# TG16_EXP_RGBSV_RevB.net
KiCad netlist of a schematic drawn in EAGLE
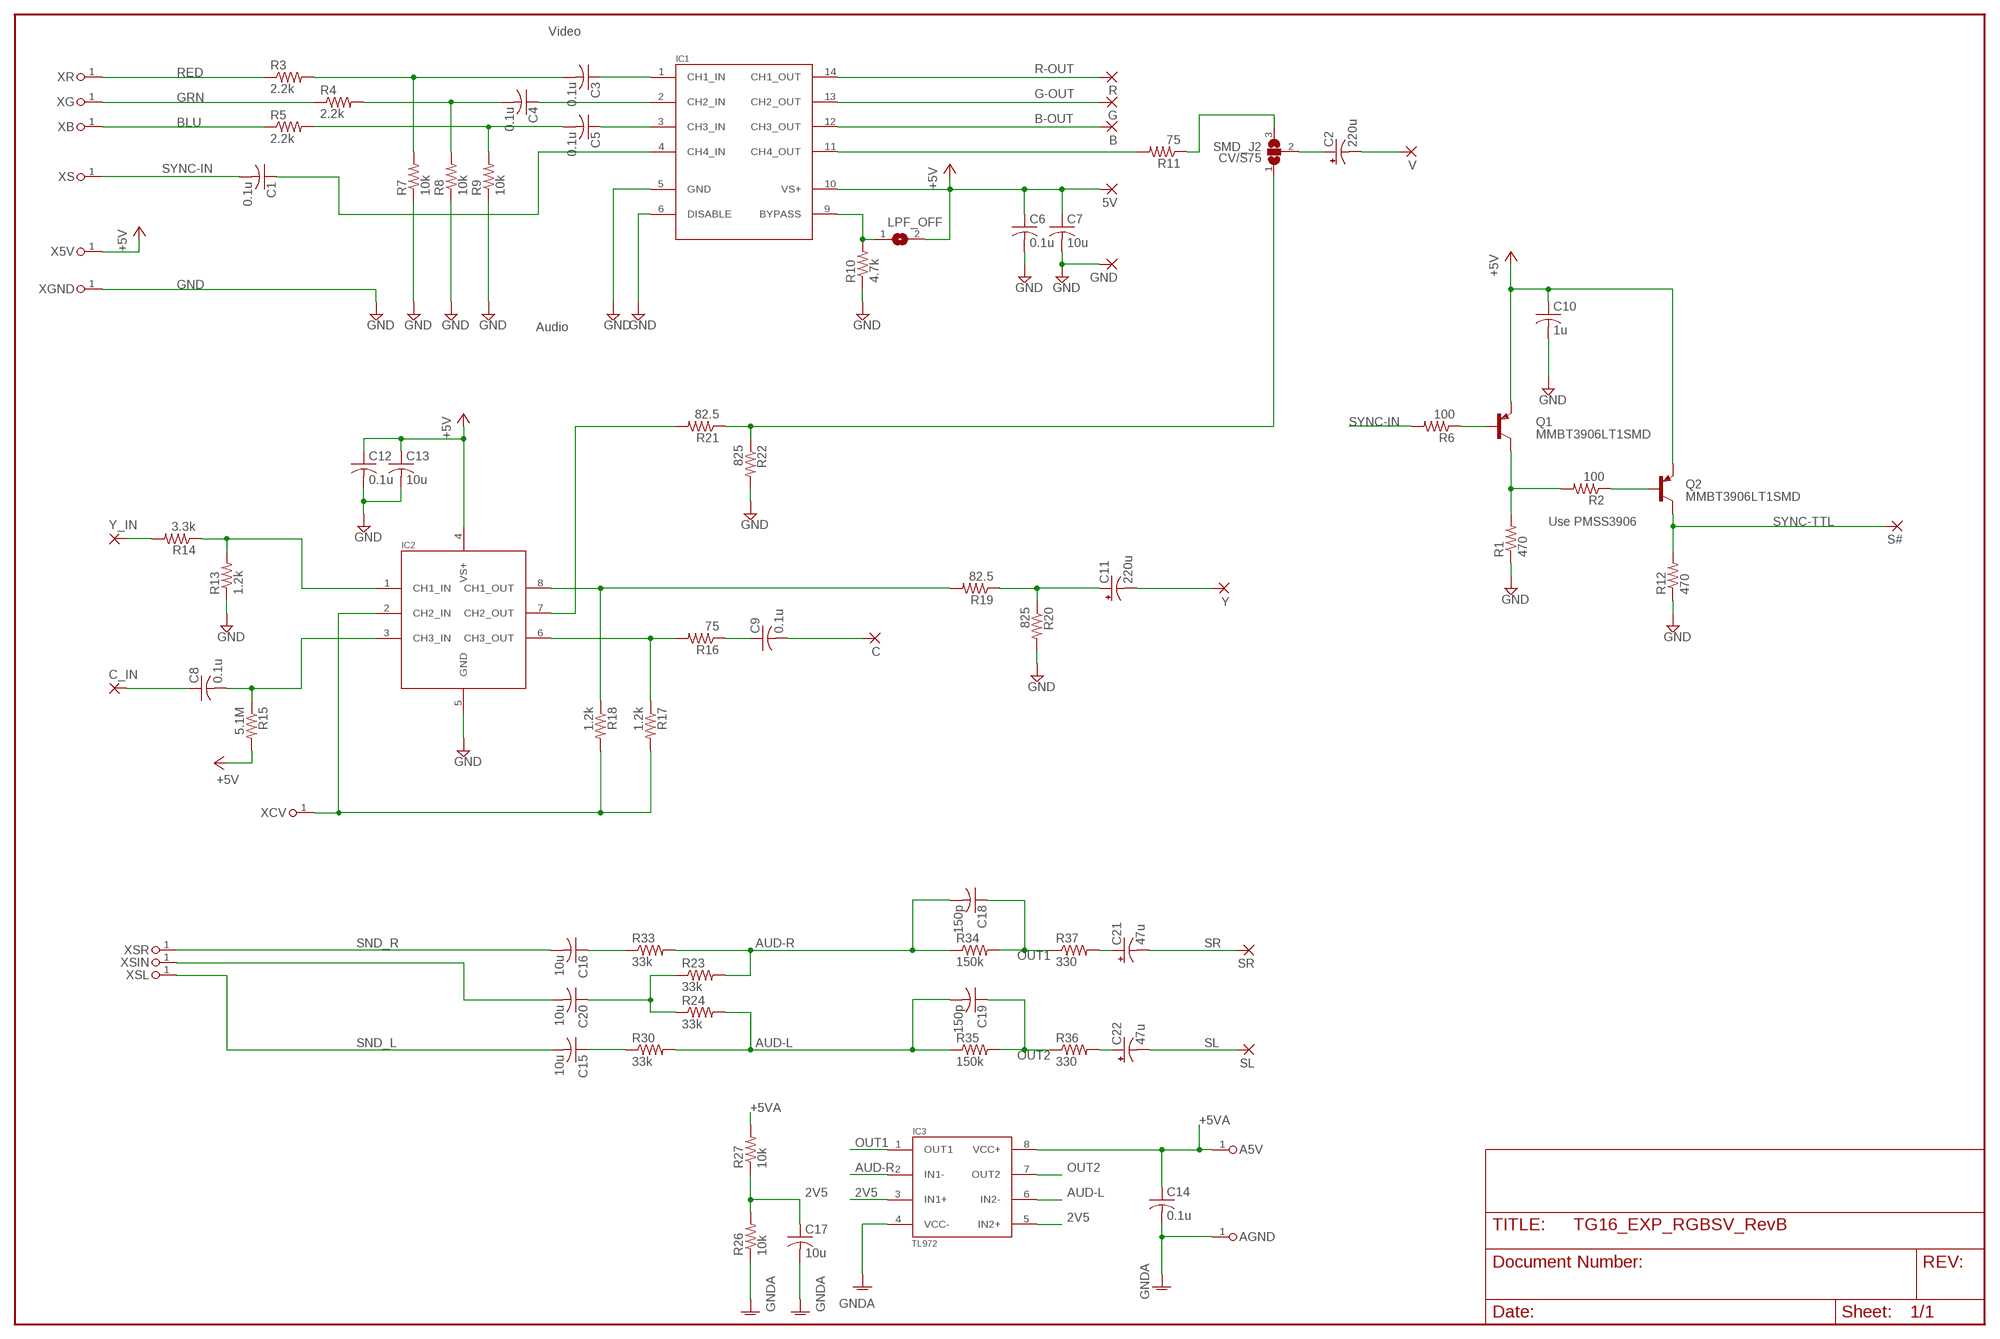
[diagram p0: schematic, sheet 1]

(export (version "E")
  (design (tool "Eeschema 10.0.6"))
  (components
    (comp (ref "5V")
      (value "SMD2")
      (footprint "eagle-import:SMD1,27-2,54")
      (libsource (lib "eagle-import") (part "SMD2"))
    )
    (comp (ref "A5V")
      (value "PINHD-1X1")
      (footprint "eagle-import:1X01")
      (libsource (lib "eagle-import") (part "PINHD-1X1"))
    )
    (comp (ref "AGND")
      (value "PINHD-1X1")
      (footprint "eagle-import:1X01")
      (libsource (lib "eagle-import") (part "PINHD-1X1"))
    )
    (comp (ref "B")
      (value "SMD2")
      (footprint "eagle-import:SMD1,27-2,54")
      (libsource (lib "eagle-import") (part "SMD2"))
    )
    (comp (ref "C")
      (value "SMD2")
      (footprint "eagle-import:SMD1,27-2,54")
      (libsource (lib "eagle-import") (part "SMD2"))
    )
    (comp (ref "C1")
      (value "0.1u")
      (footprint "eagle-import:C0603")
      (libsource (lib "eagle-import") (part "C-USC0603"))
    )
    (comp (ref "C2")
      (value "220u")
      (footprint "eagle-import:CT3528")
      (libsource (lib "eagle-import") (part "rcl_334_CPOL-USCT3528"))
    )
    (comp (ref "C3")
      (value "0.1u")
      (footprint "eagle-import:C0603")
      (libsource (lib "eagle-import") (part "C-USC0603"))
    )
    (comp (ref "C4")
      (value "0.1u")
      (footprint "eagle-import:C0603")
      (libsource (lib "eagle-import") (part "C-USC0603"))
    )
    (comp (ref "C5")
      (value "0.1u")
      (footprint "eagle-import:C0603")
      (libsource (lib "eagle-import") (part "C-USC0603"))
    )
    (comp (ref "C6")
      (value "0.1u")
      (footprint "eagle-import:C0603")
      (libsource (lib "eagle-import") (part "C-USC0603"))
    )
    (comp (ref "C7")
      (value "10u")
      (footprint "eagle-import:C1206")
      (libsource (lib "eagle-import") (part "C-USC1206"))
    )
    (comp (ref "C8")
      (value "0.1u")
      (footprint "eagle-import:C0603")
      (libsource (lib "eagle-import") (part "C-USC0603"))
    )
    (comp (ref "C9")
      (value "0.1u")
      (footprint "eagle-import:C0603")
      (libsource (lib "eagle-import") (part "C-USC0603"))
    )
    (comp (ref "C10")
      (value "1u")
      (footprint "eagle-import:C0603")
      (libsource (lib "eagle-import") (part "C-USC0603"))
    )
    (comp (ref "C11")
      (value "220u")
      (footprint "eagle-import:CT3528")
      (libsource (lib "eagle-import") (part "rcl_334_CPOL-USCT3528"))
    )
    (comp (ref "C12")
      (value "0.1u")
      (footprint "eagle-import:C0603")
      (libsource (lib "eagle-import") (part "C-USC0603"))
    )
    (comp (ref "C13")
      (value "10u")
      (footprint "eagle-import:C1206")
      (libsource (lib "eagle-import") (part "C-USC1206"))
    )
    (comp (ref "C14")
      (value "0.1u")
      (footprint "eagle-import:C0603")
      (libsource (lib "eagle-import") (part "C-USC0603"))
    )
    (comp (ref "C15")
      (value "10u")
      (footprint "eagle-import:C0805")
      (libsource (lib "eagle-import") (part "C-USC0805"))
    )
    (comp (ref "C16")
      (value "10u")
      (footprint "eagle-import:C0805")
      (libsource (lib "eagle-import") (part "C-USC0805"))
    )
    (comp (ref "C17")
      (value "10u")
      (footprint "eagle-import:C1206")
      (libsource (lib "eagle-import") (part "C-USC1206"))
    )
    (comp (ref "C18")
      (value "150p")
      (footprint "eagle-import:C0603")
      (libsource (lib "eagle-import") (part "C-USC0603"))
    )
    (comp (ref "C19")
      (value "150p")
      (footprint "eagle-import:C0603")
      (libsource (lib "eagle-import") (part "C-USC0603"))
    )
    (comp (ref "C20")
      (value "10u")
      (footprint "eagle-import:C0805")
      (libsource (lib "eagle-import") (part "C-USC0805"))
    )
    (comp (ref "C21")
      (value "47u")
      (footprint "eagle-import:CT3528")
      (libsource (lib "eagle-import") (part "CPOL-USCT3528"))
    )
    (comp (ref "C22")
      (value "47u")
      (footprint "eagle-import:CT3528")
      (libsource (lib "eagle-import") (part "CPOL-USCT3528"))
    )
    (comp (ref "CV/S75")
      (value "SMD_J2")
      (footprint "eagle-import:SJ_2")
      (libsource (lib "eagle-import") (part "SMD_J2"))
    )
    (comp (ref "C_IN")
      (value "SMD2")
      (footprint "eagle-import:SMD1,27-2,54")
      (libsource (lib "eagle-import") (part "SMD2"))
    )
    (comp (ref "G")
      (value "SMD2")
      (footprint "eagle-import:SMD1,27-2,54")
      (libsource (lib "eagle-import") (part "SMD2"))
    )
    (comp (ref "GND")
      (value "SMD2")
      (footprint "eagle-import:SMD1,27-2,54")
      (libsource (lib "eagle-import") (part "SMD2"))
    )
    (comp (ref "IC1")
      (value "THS7374TSSOP14_LONG")
      (footprint "eagle-import:TSSOP14LONG")
      (libsource (lib "eagle-import") (part "THS7374TSSOP14_LONG"))
    )
    (comp (ref "IC2")
      (value "THS7314")
      (footprint "eagle-import:SOIC8")
      (libsource (lib "eagle-import") (part "THS7314"))
    )
    (comp (ref "IC3")
      (value "TL972")
      (footprint "eagle-import:SOIC8")
      (libsource (lib "eagle-import") (part "TL972"))
    )
    (comp (ref "LPF_OFF")
      (value "SMD_J")
      (footprint "eagle-import:SJ")
      (libsource (lib "eagle-import") (part "SMD_J"))
    )
    (comp (ref "Q1")
      (value "MMBT3906LT1SMD")
      (footprint "eagle-import:SOT23-BEC")
      (libsource (lib "eagle-import") (part "MMBT3906SMDLT1"))
    )
    (comp (ref "Q2")
      (value "MMBT3906LT1SMD")
      (footprint "eagle-import:SOT23-BEC")
      (libsource (lib "eagle-import") (part "MMBT3906SMDLT1"))
    )
    (comp (ref "R")
      (value "SMD2")
      (footprint "eagle-import:SMD1,27-2,54")
      (libsource (lib "eagle-import") (part "SMD2"))
    )
    (comp (ref "R1")
      (value "470")
      (footprint "eagle-import:R0603")
      (libsource (lib "eagle-import") (part "R-US_R0603"))
    )
    (comp (ref "R2")
      (value "100")
      (footprint "eagle-import:R0603")
      (libsource (lib "eagle-import") (part "R-US_R0603"))
    )
    (comp (ref "R3")
      (value "2.2k")
      (footprint "eagle-import:R0603")
      (libsource (lib "eagle-import") (part "R-US_R0603"))
    )
    (comp (ref "R4")
      (value "2.2k")
      (footprint "eagle-import:R0603")
      (libsource (lib "eagle-import") (part "R-US_R0603"))
    )
    (comp (ref "R5")
      (value "2.2k")
      (footprint "eagle-import:R0603")
      (libsource (lib "eagle-import") (part "R-US_R0603"))
    )
    (comp (ref "R6")
      (value "100")
      (footprint "eagle-import:R0603")
      (libsource (lib "eagle-import") (part "R-US_R0603"))
    )
    (comp (ref "R7")
      (value "10k")
      (footprint "eagle-import:R0603")
      (libsource (lib "eagle-import") (part "R-US_R0603"))
    )
    (comp (ref "R8")
      (value "10k")
      (footprint "eagle-import:R0603")
      (libsource (lib "eagle-import") (part "R-US_R0603"))
    )
    (comp (ref "R9")
      (value "10k")
      (footprint "eagle-import:R0603")
      (libsource (lib "eagle-import") (part "R-US_R0603"))
    )
    (comp (ref "R10")
      (value "4.7k")
      (footprint "eagle-import:R0603")
      (libsource (lib "eagle-import") (part "R-US_R0603"))
    )
    (comp (ref "R11")
      (value "75")
      (footprint "eagle-import:R0603")
      (libsource (lib "eagle-import") (part "R-US_R0603"))
    )
    (comp (ref "R12")
      (value "470")
      (footprint "eagle-import:R0603")
      (libsource (lib "eagle-import") (part "R-US_R0603"))
    )
    (comp (ref "R13")
      (value "1.2k")
      (footprint "eagle-import:R0603")
      (libsource (lib "eagle-import") (part "R-US_R0603"))
    )
    (comp (ref "R14")
      (value "3.3k")
      (footprint "eagle-import:R0603")
      (libsource (lib "eagle-import") (part "R-US_R0603"))
    )
    (comp (ref "R15")
      (value "5.1M")
      (footprint "eagle-import:R0603")
      (libsource (lib "eagle-import") (part "R-US_R0603"))
    )
    (comp (ref "R16")
      (value "75")
      (footprint "eagle-import:R0603")
      (libsource (lib "eagle-import") (part "R-US_R0603"))
    )
    (comp (ref "R17")
      (value "1.2k")
      (footprint "eagle-import:R0603")
      (libsource (lib "eagle-import") (part "R-US_R0603"))
    )
    (comp (ref "R18")
      (value "1.2k")
      (footprint "eagle-import:R0603")
      (libsource (lib "eagle-import") (part "R-US_R0603"))
    )
    (comp (ref "R19")
      (value "82.5")
      (footprint "eagle-import:R0603")
      (libsource (lib "eagle-import") (part "R-US_R0603"))
    )
    (comp (ref "R20")
      (value "825")
      (footprint "eagle-import:R0603")
      (libsource (lib "eagle-import") (part "R-US_R0603"))
    )
    (comp (ref "R21")
      (value "82.5")
      (footprint "eagle-import:R0603")
      (libsource (lib "eagle-import") (part "R-US_R0603"))
    )
    (comp (ref "R22")
      (value "825")
      (footprint "eagle-import:R0603")
      (libsource (lib "eagle-import") (part "R-US_R0603"))
    )
    (comp (ref "R23")
      (value "33k")
      (footprint "eagle-import:R0603")
      (libsource (lib "eagle-import") (part "R-US_R0603"))
    )
    (comp (ref "R24")
      (value "33k")
      (footprint "eagle-import:R0603")
      (libsource (lib "eagle-import") (part "R-US_R0603"))
    )
    (comp (ref "R26")
      (value "10k")
      (footprint "eagle-import:R0603")
      (libsource (lib "eagle-import") (part "R-US_R0603"))
    )
    (comp (ref "R27")
      (value "10k")
      (footprint "eagle-import:R0603")
      (libsource (lib "eagle-import") (part "R-US_R0603"))
    )
    (comp (ref "R30")
      (value "33k")
      (footprint "eagle-import:R0603")
      (libsource (lib "eagle-import") (part "R-US_R0603"))
    )
    (comp (ref "R33")
      (value "33k")
      (footprint "eagle-import:R0603")
      (libsource (lib "eagle-import") (part "R-US_R0603"))
    )
    (comp (ref "R34")
      (value "150k")
      (footprint "eagle-import:R0603")
      (libsource (lib "eagle-import") (part "R-US_R0603"))
    )
    (comp (ref "R35")
      (value "150k")
      (footprint "eagle-import:R0603")
      (libsource (lib "eagle-import") (part "R-US_R0603"))
    )
    (comp (ref "R36")
      (value "330")
      (footprint "eagle-import:R0603")
      (libsource (lib "eagle-import") (part "R-US_R0603"))
    )
    (comp (ref "R37")
      (value "330")
      (footprint "eagle-import:R0603")
      (libsource (lib "eagle-import") (part "R-US_R0603"))
    )
    (comp (ref "S#")
      (value "SMD2")
      (footprint "eagle-import:SMD1,27-2,54")
      (libsource (lib "eagle-import") (part "SMD2"))
    )
    (comp (ref "SL")
      (value "SMD2")
      (footprint "eagle-import:SMD1,27-2,54")
      (libsource (lib "eagle-import") (part "SMD2"))
    )
    (comp (ref "SR")
      (value "SMD2")
      (footprint "eagle-import:SMD1,27-2,54")
      (libsource (lib "eagle-import") (part "SMD2"))
    )
    (comp (ref "V")
      (value "SMD2")
      (footprint "eagle-import:SMD1,27-2,54")
      (libsource (lib "eagle-import") (part "SMD2"))
    )
    (comp (ref "X5V")
      (value "PINHD-1X1")
      (footprint "eagle-import:1X01")
      (libsource (lib "eagle-import") (part "PINHD-1X1"))
    )
    (comp (ref "XB")
      (value "PINHD-1X1")
      (footprint "eagle-import:1X01")
      (libsource (lib "eagle-import") (part "PINHD-1X1"))
    )
    (comp (ref "XCV")
      (value "PINHD-1X1")
      (footprint "eagle-import:1X01")
      (libsource (lib "eagle-import") (part "PINHD-1X1"))
    )
    (comp (ref "XG")
      (value "PINHD-1X1")
      (footprint "eagle-import:1X01")
      (libsource (lib "eagle-import") (part "PINHD-1X1"))
    )
    (comp (ref "XGND")
      (value "PINHD-1X1")
      (footprint "eagle-import:1X01")
      (libsource (lib "eagle-import") (part "PINHD-1X1"))
    )
    (comp (ref "XR")
      (value "PINHD-1X1")
      (footprint "eagle-import:1X01")
      (libsource (lib "eagle-import") (part "PINHD-1X1"))
    )
    (comp (ref "XS")
      (value "PINHD-1X1")
      (footprint "eagle-import:1X01")
      (libsource (lib "eagle-import") (part "PINHD-1X1"))
    )
    (comp (ref "XSIN")
      (value "PINHD-1X1")
      (footprint "eagle-import:1X01")
      (libsource (lib "eagle-import") (part "PINHD-1X1"))
    )
    (comp (ref "XSL")
      (value "PINHD-1X1")
      (footprint "eagle-import:1X01")
      (libsource (lib "eagle-import") (part "PINHD-1X1"))
    )
    (comp (ref "XSR")
      (value "PINHD-1X1")
      (footprint "eagle-import:1X01")
      (libsource (lib "eagle-import") (part "PINHD-1X1"))
    )
    (comp (ref "Y")
      (value "SMD2")
      (footprint "eagle-import:SMD1,27-2,54")
      (libsource (lib "eagle-import") (part "SMD2"))
    )
    (comp (ref "Y_IN")
      (value "SMD2")
      (footprint "eagle-import:SMD1,27-2,54")
      (libsource (lib "eagle-import") (part "SMD2"))
    )
  )
  (nets
    (net (code "1") (name "+5V") (class "Default")
      (node (ref "5V") (pin "1") (pinfunction "P_1") (pintype "passive"))
      (node (ref "C10") (pin "1") (pinfunction "1_1") (pintype "passive"))
      (node (ref "C12") (pin "1") (pinfunction "1_1") (pintype "passive"))
      (node (ref "C13") (pin "1") (pinfunction "1_1") (pintype "passive"))
      (node (ref "C6") (pin "1") (pinfunction "1_1") (pintype "passive"))
      (node (ref "C7") (pin "1") (pinfunction "1_1") (pintype "passive"))
      (node (ref "IC1") (pin "10") (pinfunction "VS+_10") (pintype "bidirectional"))
      (node (ref "IC2") (pin "4") (pinfunction "VS+_4") (pintype "bidirectional"))
      (node (ref "LPF_OFF") (pin "2") (pinfunction "2_2") (pintype "passive"))
      (node (ref "Q1") (pin "E") (pinfunction "E_E") (pintype "passive"))
      (node (ref "Q2") (pin "E") (pinfunction "E_E") (pintype "passive"))
      (node (ref "R15") (pin "2") (pinfunction "2_2") (pintype "passive"))
      (node (ref "X5V") (pin "1") (pinfunction "1_1") (pintype "passive"))
    )
    (net (code "2") (name "/+5VA") (class "Default")
      (node (ref "A5V") (pin "1") (pinfunction "1_1") (pintype "passive"))
      (node (ref "C14") (pin "1") (pinfunction "1_1") (pintype "passive"))
      (node (ref "IC3") (pin "8") (pinfunction "VCC+_8") (pintype "bidirectional"))
      (node (ref "R27") (pin "2") (pinfunction "2_2") (pintype "passive"))
    )
    (net (code "3") (name "/2V5") (class "Default")
      (node (ref "C17") (pin "1") (pinfunction "1_1") (pintype "passive"))
      (node (ref "IC3") (pin "3") (pinfunction "IN1+_3") (pintype "bidirectional"))
      (node (ref "IC3") (pin "5") (pinfunction "IN2+_5") (pintype "bidirectional"))
      (node (ref "R26") (pin "2") (pinfunction "2_2") (pintype "passive"))
      (node (ref "R27") (pin "1") (pinfunction "1_1") (pintype "passive"))
    )
    (net (code "4") (name "/AUD-L") (class "Default")
      (node (ref "C19") (pin "2") (pinfunction "2_2") (pintype "passive"))
      (node (ref "IC3") (pin "6") (pinfunction "IN2-_6") (pintype "bidirectional"))
      (node (ref "R24") (pin "2") (pinfunction "2_2") (pintype "passive"))
      (node (ref "R30") (pin "2") (pinfunction "2_2") (pintype "passive"))
      (node (ref "R35") (pin "1") (pinfunction "1_1") (pintype "passive"))
    )
    (net (code "5") (name "/AUD-R") (class "Default")
      (node (ref "C18") (pin "2") (pinfunction "2_2") (pintype "passive"))
      (node (ref "IC3") (pin "2") (pinfunction "IN1-_2") (pintype "bidirectional"))
      (node (ref "R23") (pin "2") (pinfunction "2_2") (pintype "passive"))
      (node (ref "R33") (pin "2") (pinfunction "2_2") (pintype "passive"))
      (node (ref "R34") (pin "1") (pinfunction "1_1") (pintype "passive"))
    )
    (net (code "6") (name "/B-OUT") (class "Default")
      (node (ref "B") (pin "1") (pinfunction "P_1") (pintype "passive"))
      (node (ref "IC1") (pin "12") (pinfunction "CH3_OUT_12") (pintype "bidirectional"))
    )
    (net (code "7") (name "/BLU") (class "Default")
      (node (ref "R5") (pin "1") (pinfunction "1_1") (pintype "passive"))
      (node (ref "XB") (pin "1") (pinfunction "1_1") (pintype "passive"))
    )
    (net (code "8") (name "/G-OUT") (class "Default")
      (node (ref "G") (pin "1") (pinfunction "P_1") (pintype "passive"))
      (node (ref "IC1") (pin "13") (pinfunction "CH2_OUT_13") (pintype "bidirectional"))
    )
    (net (code "9") (name "/GRN") (class "Default")
      (node (ref "R4") (pin "1") (pinfunction "1_1") (pintype "passive"))
      (node (ref "XG") (pin "1") (pinfunction "1_1") (pintype "passive"))
    )
    (net (code "10") (name "/OUT1") (class "Default")
      (node (ref "C18") (pin "1") (pinfunction "1_1") (pintype "passive"))
      (node (ref "IC3") (pin "1") (pinfunction "OUT1_1") (pintype "bidirectional"))
      (node (ref "R34") (pin "2") (pinfunction "2_2") (pintype "passive"))
      (node (ref "R37") (pin "1") (pinfunction "1_1") (pintype "passive"))
    )
    (net (code "11") (name "/OUT2") (class "Default")
      (node (ref "C19") (pin "1") (pinfunction "1_1") (pintype "passive"))
      (node (ref "IC3") (pin "7") (pinfunction "OUT2_7") (pintype "bidirectional"))
      (node (ref "R35") (pin "2") (pinfunction "2_2") (pintype "passive"))
      (node (ref "R36") (pin "1") (pinfunction "1_1") (pintype "passive"))
    )
    (net (code "12") (name "/R-OUT") (class "Default")
      (node (ref "IC1") (pin "14") (pinfunction "CH1_OUT_14") (pintype "bidirectional"))
      (node (ref "R") (pin "1") (pinfunction "P_1") (pintype "passive"))
    )
    (net (code "13") (name "/RED") (class "Default")
      (node (ref "R3") (pin "1") (pinfunction "1_1") (pintype "passive"))
      (node (ref "XR") (pin "1") (pinfunction "1_1") (pintype "passive"))
    )
    (net (code "14") (name "/SL") (class "Default")
      (node (ref "C22") (pin "-") (pinfunction "-_-") (pintype "passive"))
      (node (ref "SL") (pin "1") (pinfunction "P_1") (pintype "passive"))
    )
    (net (code "15") (name "/SND_L") (class "Default")
      (node (ref "C15") (pin "2") (pinfunction "2_2") (pintype "passive"))
      (node (ref "XSL") (pin "1") (pinfunction "1_1") (pintype "passive"))
    )
    (net (code "16") (name "/SND_R") (class "Default")
      (node (ref "C16") (pin "2") (pinfunction "2_2") (pintype "passive"))
      (node (ref "XSR") (pin "1") (pinfunction "1_1") (pintype "passive"))
    )
    (net (code "17") (name "/SR") (class "Default")
      (node (ref "C21") (pin "-") (pinfunction "-_-") (pintype "passive"))
      (node (ref "SR") (pin "1") (pinfunction "P_1") (pintype "passive"))
    )
    (net (code "18") (name "/SYNC-IN") (class "Default")
      (node (ref "C1") (pin "2") (pinfunction "2_2") (pintype "passive"))
      (node (ref "R6") (pin "2") (pinfunction "2_2") (pintype "passive"))
      (node (ref "XS") (pin "1") (pinfunction "1_1") (pintype "passive"))
    )
    (net (code "19") (name "/SYNC-TTL") (class "Default")
      (node (ref "Q2") (pin "C") (pinfunction "C_C") (pintype "passive"))
      (node (ref "R12") (pin "2") (pinfunction "2_2") (pintype "passive"))
      (node (ref "S#") (pin "1") (pinfunction "P_1") (pintype "passive"))
    )
    (net (code "20") (name "GND") (class "Default")
      (node (ref "C10") (pin "2") (pinfunction "2_2") (pintype "passive"))
      (node (ref "C12") (pin "2") (pinfunction "2_2") (pintype "passive"))
      (node (ref "C13") (pin "2") (pinfunction "2_2") (pintype "passive"))
      (node (ref "C6") (pin "2") (pinfunction "2_2") (pintype "passive"))
      (node (ref "C7") (pin "2") (pinfunction "2_2") (pintype "passive"))
      (node (ref "GND") (pin "1") (pinfunction "P_1") (pintype "passive"))
      (node (ref "IC1") (pin "5") (pinfunction "GND_5") (pintype "bidirectional"))
      (node (ref "IC1") (pin "6") (pinfunction "DISABLE_6") (pintype "bidirectional"))
      (node (ref "IC2") (pin "5") (pinfunction "GND_5") (pintype "bidirectional"))
      (node (ref "R1") (pin "1") (pinfunction "1_1") (pintype "passive"))
      (node (ref "R10") (pin "1") (pinfunction "1_1") (pintype "passive"))
      (node (ref "R12") (pin "1") (pinfunction "1_1") (pintype "passive"))
      (node (ref "R13") (pin "1") (pinfunction "1_1") (pintype "passive"))
      (node (ref "R20") (pin "2") (pinfunction "2_2") (pintype "passive"))
      (node (ref "R22") (pin "2") (pinfunction "2_2") (pintype "passive"))
      (node (ref "R7") (pin "1") (pinfunction "1_1") (pintype "passive"))
      (node (ref "R8") (pin "1") (pinfunction "1_1") (pintype "passive"))
      (node (ref "R9") (pin "1") (pinfunction "1_1") (pintype "passive"))
      (node (ref "XGND") (pin "1") (pinfunction "1_1") (pintype "passive"))
    )
    (net (code "21") (name "GNDA") (class "Default")
      (node (ref "AGND") (pin "1") (pinfunction "1_1") (pintype "passive"))
      (node (ref "C14") (pin "2") (pinfunction "2_2") (pintype "passive"))
      (node (ref "C17") (pin "2") (pinfunction "2_2") (pintype "passive"))
      (node (ref "IC3") (pin "4") (pinfunction "VCC-_4") (pintype "bidirectional"))
      (node (ref "R26") (pin "1") (pinfunction "1_1") (pintype "passive"))
    )
    (net (code "22") (name "Net-(C-P)") (class "Default")
      (node (ref "C") (pin "1") (pinfunction "P_1") (pintype "passive"))
      (node (ref "C9") (pin "2") (pinfunction "2_2") (pintype "passive"))
    )
    (net (code "23") (name "Net-(C2-Pad+)") (class "Default")
      (node (ref "C2") (pin "+") (pinfunction "+_+") (pintype "passive"))
      (node (ref "CV/S75") (pin "2") (pinfunction "2_2") (pintype "passive"))
    )
    (net (code "24") (name "Net-(C3-Pad2)") (class "Default")
      (node (ref "C3") (pin "2") (pinfunction "2_2") (pintype "passive"))
      (node (ref "R3") (pin "2") (pinfunction "2_2") (pintype "passive"))
      (node (ref "R7") (pin "2") (pinfunction "2_2") (pintype "passive"))
    )
    (net (code "25") (name "Net-(C4-Pad2)") (class "Default")
      (node (ref "C4") (pin "2") (pinfunction "2_2") (pintype "passive"))
      (node (ref "R4") (pin "2") (pinfunction "2_2") (pintype "passive"))
      (node (ref "R8") (pin "2") (pinfunction "2_2") (pintype "passive"))
    )
    (net (code "26") (name "Net-(C5-Pad2)") (class "Default")
      (node (ref "C5") (pin "2") (pinfunction "2_2") (pintype "passive"))
      (node (ref "R5") (pin "2") (pinfunction "2_2") (pintype "passive"))
      (node (ref "R9") (pin "2") (pinfunction "2_2") (pintype "passive"))
    )
    (net (code "27") (name "Net-(C9-Pad1)") (class "Default")
      (node (ref "C9") (pin "1") (pinfunction "1_1") (pintype "passive"))
      (node (ref "R16") (pin "1") (pinfunction "1_1") (pintype "passive"))
    )
    (net (code "28") (name "Net-(C11-Pad+)") (class "Default")
      (node (ref "C11") (pin "+") (pinfunction "+_+") (pintype "passive"))
      (node (ref "R19") (pin "1") (pinfunction "1_1") (pintype "passive"))
      (node (ref "R20") (pin "1") (pinfunction "1_1") (pintype "passive"))
    )
    (net (code "29") (name "Net-(C15-Pad1)") (class "Default")
      (node (ref "C15") (pin "1") (pinfunction "1_1") (pintype "passive"))
      (node (ref "R30") (pin "1") (pinfunction "1_1") (pintype "passive"))
    )
    (net (code "30") (name "Net-(C16-Pad1)") (class "Default")
      (node (ref "C16") (pin "1") (pinfunction "1_1") (pintype "passive"))
      (node (ref "R33") (pin "1") (pinfunction "1_1") (pintype "passive"))
    )
    (net (code "31") (name "Net-(C20-Pad1)") (class "Default")
      (node (ref "C20") (pin "1") (pinfunction "1_1") (pintype "passive"))
      (node (ref "R23") (pin "1") (pinfunction "1_1") (pintype "passive"))
      (node (ref "R24") (pin "1") (pinfunction "1_1") (pintype "passive"))
    )
    (net (code "32") (name "Net-(C20-Pad2)") (class "Default")
      (node (ref "C20") (pin "2") (pinfunction "2_2") (pintype "passive"))
      (node (ref "XSIN") (pin "1") (pinfunction "1_1") (pintype "passive"))
    )
    (net (code "33") (name "Net-(C21-Pad+)") (class "Default")
      (node (ref "C21") (pin "+") (pinfunction "+_+") (pintype "passive"))
      (node (ref "R37") (pin "2") (pinfunction "2_2") (pintype "passive"))
    )
    (net (code "34") (name "Net-(C22-Pad+)") (class "Default")
      (node (ref "C22") (pin "+") (pinfunction "+_+") (pintype "passive"))
      (node (ref "R36") (pin "2") (pinfunction "2_2") (pintype "passive"))
    )
    (net (code "35") (name "Net-(CV/S75-Pad1)") (class "Default")
      (node (ref "CV/S75") (pin "1") (pinfunction "1_1") (pintype "passive"))
      (node (ref "R21") (pin "1") (pinfunction "1_1") (pintype "passive"))
      (node (ref "R22") (pin "1") (pinfunction "1_1") (pintype "passive"))
    )
    (net (code "36") (name "Net-(CV/S75-Pad3)") (class "Default")
      (node (ref "CV/S75") (pin "3") (pinfunction "3_3") (pintype "passive"))
      (node (ref "R11") (pin "1") (pinfunction "1_1") (pintype "passive"))
    )
    (net (code "37") (name "Net-(C_IN-P)") (class "Default")
      (node (ref "C8") (pin "1") (pinfunction "1_1") (pintype "passive"))
      (node (ref "C_IN") (pin "1") (pinfunction "P_1") (pintype "passive"))
    )
    (net (code "38") (name "Net-(IC1-BYPASS)") (class "Default")
      (node (ref "IC1") (pin "9") (pinfunction "BYPASS_9") (pintype "bidirectional"))
      (node (ref "LPF_OFF") (pin "1") (pinfunction "1_1") (pintype "passive"))
      (node (ref "R10") (pin "2") (pinfunction "2_2") (pintype "passive"))
    )
    (net (code "39") (name "Net-(IC1-CH1_IN)") (class "Default")
      (node (ref "C3") (pin "1") (pinfunction "1_1") (pintype "passive"))
      (node (ref "IC1") (pin "1") (pinfunction "CH1_IN_1") (pintype "bidirectional"))
    )
    (net (code "40") (name "Net-(IC1-CH2_IN)") (class "Default")
      (node (ref "C4") (pin "1") (pinfunction "1_1") (pintype "passive"))
      (node (ref "IC1") (pin "2") (pinfunction "CH2_IN_2") (pintype "bidirectional"))
    )
    (net (code "41") (name "Net-(IC1-CH3_IN)") (class "Default")
      (node (ref "C5") (pin "1") (pinfunction "1_1") (pintype "passive"))
      (node (ref "IC1") (pin "3") (pinfunction "CH3_IN_3") (pintype "bidirectional"))
    )
    (net (code "42") (name "Net-(IC1-CH4_IN)") (class "Default")
      (node (ref "C1") (pin "1") (pinfunction "1_1") (pintype "passive"))
      (node (ref "IC1") (pin "4") (pinfunction "CH4_IN_4") (pintype "bidirectional"))
    )
    (net (code "43") (name "Net-(IC1-CH4_OUT)") (class "Default")
      (node (ref "IC1") (pin "11") (pinfunction "CH4_OUT_11") (pintype "bidirectional"))
      (node (ref "R11") (pin "2") (pinfunction "2_2") (pintype "passive"))
    )
    (net (code "44") (name "Net-(IC2-CH1_IN)") (class "Default")
      (node (ref "IC2") (pin "1") (pinfunction "CH1_IN_1") (pintype "bidirectional"))
      (node (ref "R13") (pin "2") (pinfunction "2_2") (pintype "passive"))
      (node (ref "R14") (pin "1") (pinfunction "1_1") (pintype "passive"))
    )
    (net (code "45") (name "Net-(IC2-CH1_OUT)") (class "Default")
      (node (ref "IC2") (pin "8") (pinfunction "CH1_OUT_8") (pintype "bidirectional"))
      (node (ref "R18") (pin "1") (pinfunction "1_1") (pintype "passive"))
      (node (ref "R19") (pin "2") (pinfunction "2_2") (pintype "passive"))
    )
    (net (code "46") (name "Net-(IC2-CH2_IN)") (class "Default")
      (node (ref "IC2") (pin "2") (pinfunction "CH2_IN_2") (pintype "bidirectional"))
      (node (ref "R17") (pin "2") (pinfunction "2_2") (pintype "passive"))
      (node (ref "R18") (pin "2") (pinfunction "2_2") (pintype "passive"))
      (node (ref "XCV") (pin "1") (pinfunction "1_1") (pintype "passive"))
    )
    (net (code "47") (name "Net-(IC2-CH2_OUT)") (class "Default")
      (node (ref "IC2") (pin "7") (pinfunction "CH2_OUT_7") (pintype "bidirectional"))
      (node (ref "R21") (pin "2") (pinfunction "2_2") (pintype "passive"))
    )
    (net (code "48") (name "Net-(IC2-CH3_IN)") (class "Default")
      (node (ref "C8") (pin "2") (pinfunction "2_2") (pintype "passive"))
      (node (ref "IC2") (pin "3") (pinfunction "CH3_IN_3") (pintype "bidirectional"))
      (node (ref "R15") (pin "1") (pinfunction "1_1") (pintype "passive"))
    )
    (net (code "49") (name "Net-(IC2-CH3_OUT)") (class "Default")
      (node (ref "IC2") (pin "6") (pinfunction "CH3_OUT_6") (pintype "bidirectional"))
      (node (ref "R16") (pin "2") (pinfunction "2_2") (pintype "passive"))
      (node (ref "R17") (pin "1") (pinfunction "1_1") (pintype "passive"))
    )
    (net (code "50") (name "Net-(Q1-PadB)") (class "Default")
      (node (ref "Q1") (pin "B") (pinfunction "B_B") (pintype "passive"))
      (node (ref "R6") (pin "1") (pinfunction "1_1") (pintype "passive"))
    )
    (net (code "51") (name "Net-(Q1-PadC)") (class "Default")
      (node (ref "Q1") (pin "C") (pinfunction "C_C") (pintype "passive"))
      (node (ref "R1") (pin "2") (pinfunction "2_2") (pintype "passive"))
      (node (ref "R2") (pin "2") (pinfunction "2_2") (pintype "passive"))
    )
    (net (code "52") (name "Net-(Q2-PadB)") (class "Default")
      (node (ref "Q2") (pin "B") (pinfunction "B_B") (pintype "passive"))
      (node (ref "R2") (pin "1") (pinfunction "1_1") (pintype "passive"))
    )
    (net (code "53") (name "Net-(V-P)") (class "Default")
      (node (ref "C2") (pin "-") (pinfunction "-_-") (pintype "passive"))
      (node (ref "V") (pin "1") (pinfunction "P_1") (pintype "passive"))
    )
    (net (code "54") (name "Net-(Y-P)") (class "Default")
      (node (ref "C11") (pin "-") (pinfunction "-_-") (pintype "passive"))
      (node (ref "Y") (pin "1") (pinfunction "P_1") (pintype "passive"))
    )
    (net (code "55") (name "Net-(Y_IN-P)") (class "Default")
      (node (ref "R14") (pin "2") (pinfunction "2_2") (pintype "passive"))
      (node (ref "Y_IN") (pin "1") (pinfunction "P_1") (pintype "passive"))
    )
  )
)
